# 2_waffling60-MX_matrix.net
KiCad netlist of a schematic drawn in Altium Designer
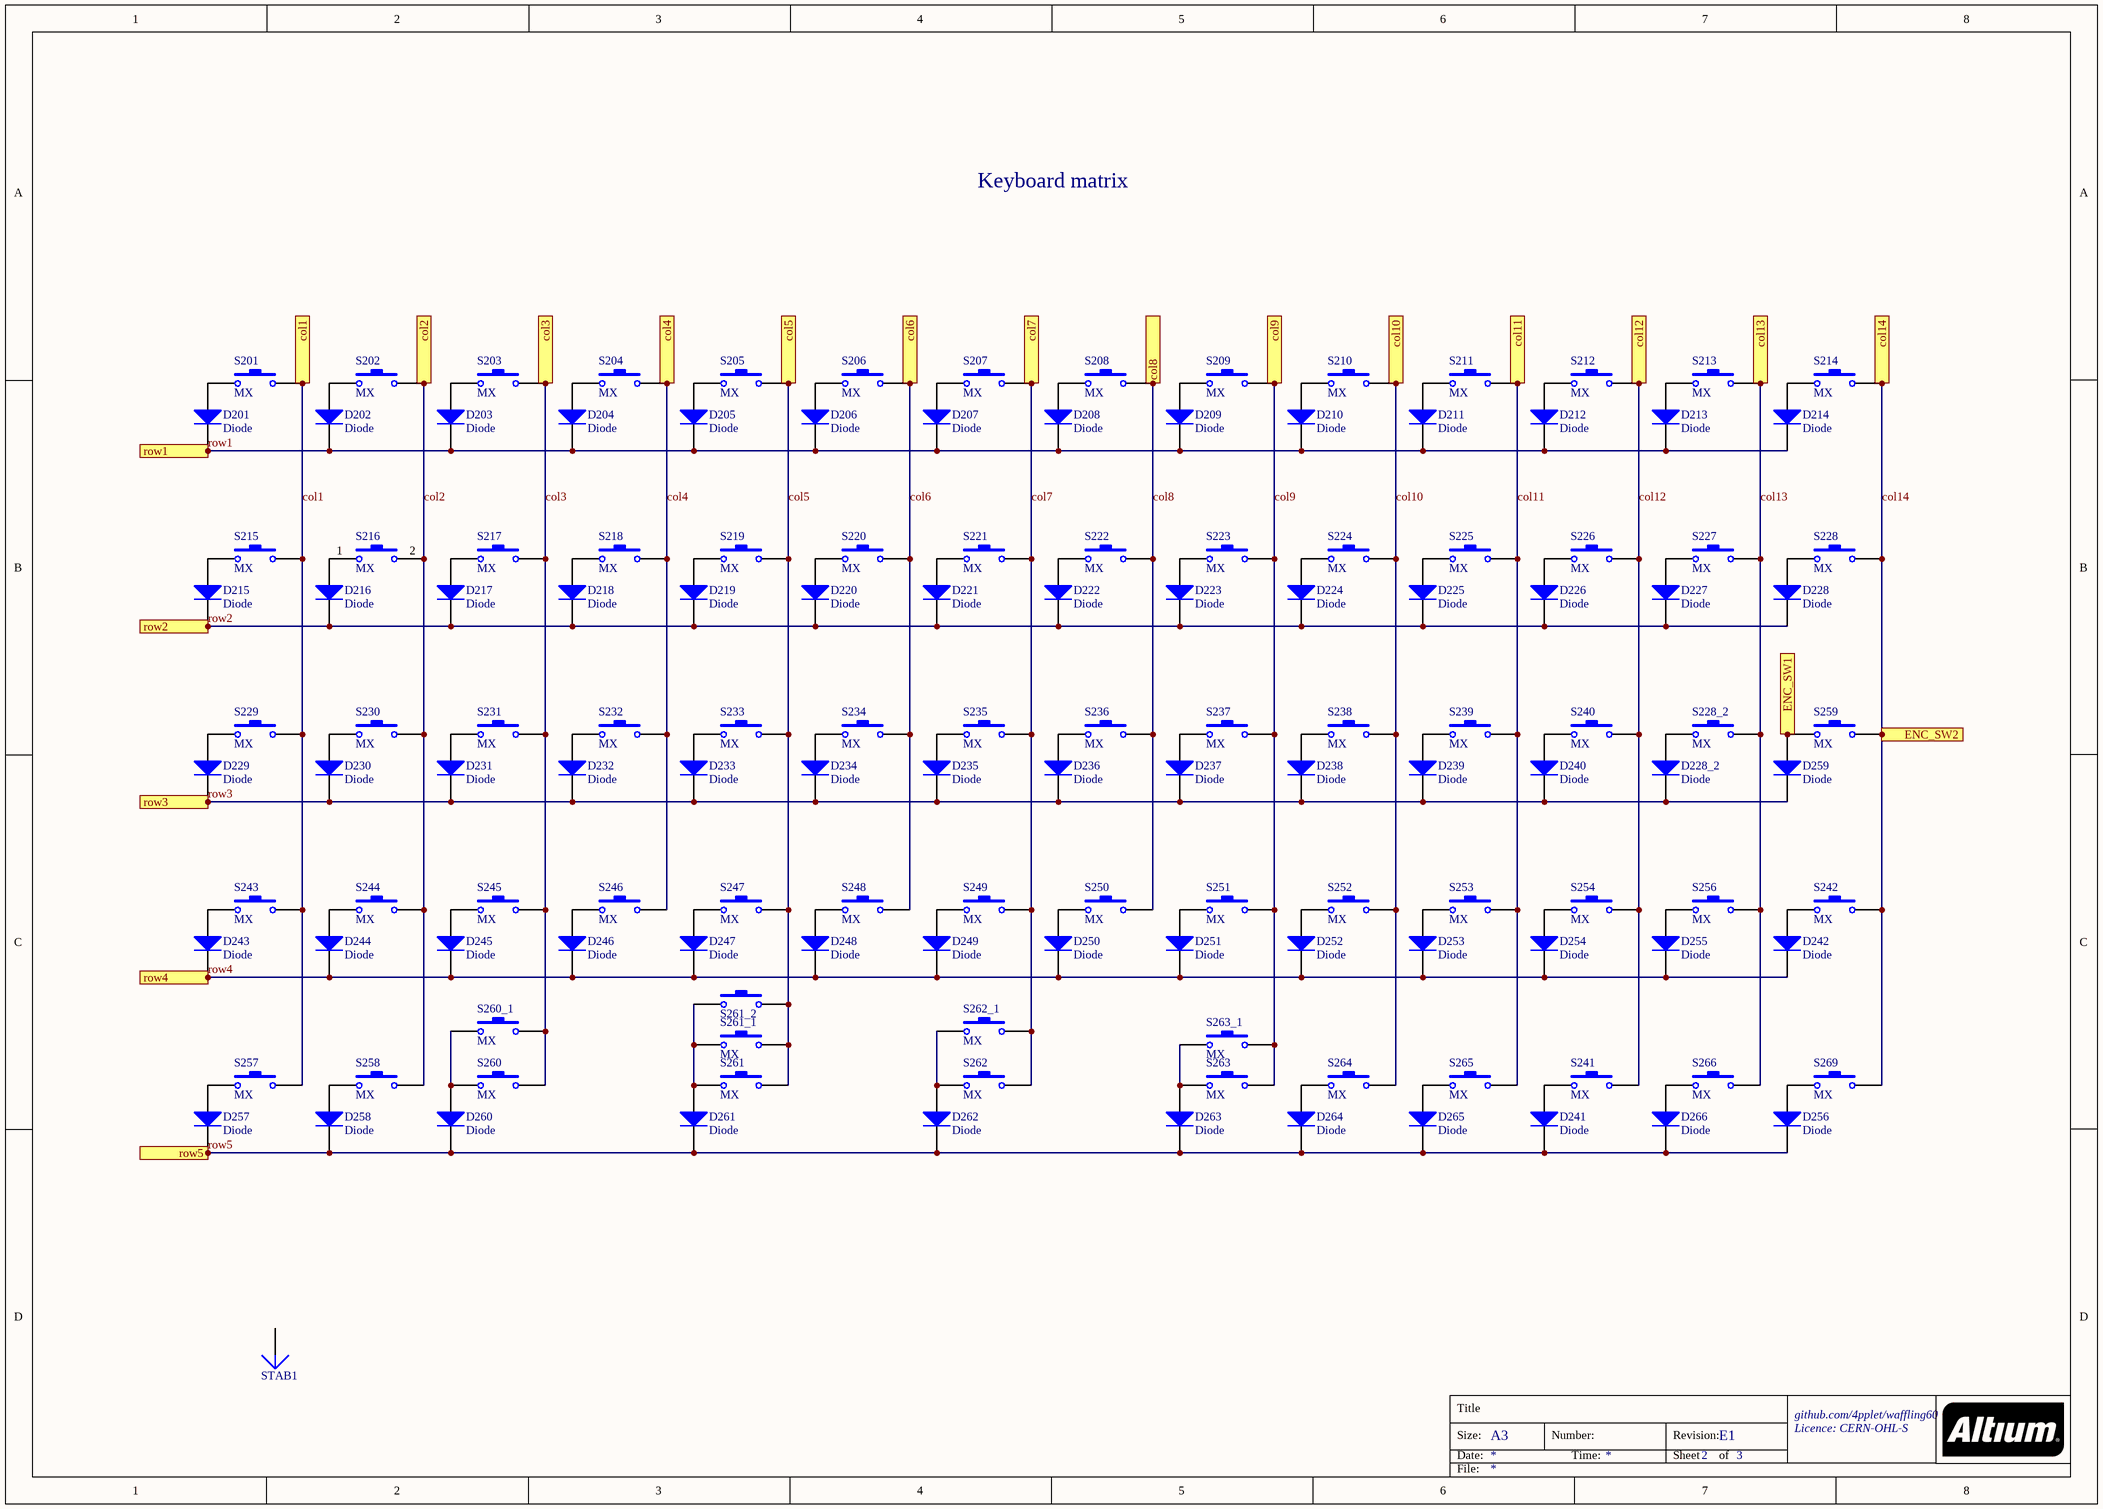
[diagram p0: 2_waffling60-MX_matrix.SchDoc]

(export (version "E")
  (design (tool "Eeschema 10.0.6"))
  (components
    (comp (ref "D201")
      (value "Diode")
      (footprint "SOD-123")
      (description "Default Diode")
      (fields (field (name "LCSC PART #") "C81598") (field (name "MRF.PART") "1N4148W"))
      (libsource (lib "Miscellaneous Devices") (part "Diode"))
    )
    (comp (ref "D202")
      (value "Diode")
      (footprint "SOD-123")
      (description "Default Diode")
      (fields (field (name "LCSC PART #") "C81598") (field (name "MRF.PART") "1N4148W"))
      (libsource (lib "Miscellaneous Devices") (part "Diode"))
    )
    (comp (ref "D203")
      (value "Diode")
      (footprint "SOD-123")
      (description "Default Diode")
      (fields (field (name "LCSC PART #") "C81598") (field (name "MRF.PART") "1N4148W"))
      (libsource (lib "Miscellaneous Devices") (part "Diode"))
    )
    (comp (ref "D204")
      (value "Diode")
      (footprint "SOD-123")
      (description "Default Diode")
      (fields (field (name "LCSC PART #") "C81598") (field (name "MRF.PART") "1N4148W"))
      (libsource (lib "Miscellaneous Devices") (part "Diode"))
    )
    (comp (ref "D205")
      (value "Diode")
      (footprint "SOD-123")
      (description "Default Diode")
      (fields (field (name "LCSC PART #") "C81598") (field (name "MRF.PART") "1N4148W"))
      (libsource (lib "Miscellaneous Devices") (part "Diode"))
    )
    (comp (ref "D206")
      (value "Diode")
      (footprint "SOD-123")
      (description "Default Diode")
      (fields (field (name "LCSC PART #") "C81598") (field (name "MRF.PART") "1N4148W"))
      (libsource (lib "Miscellaneous Devices") (part "Diode"))
    )
    (comp (ref "D207")
      (value "Diode")
      (footprint "SOD-123")
      (description "Default Diode")
      (fields (field (name "LCSC PART #") "C81598") (field (name "MRF.PART") "1N4148W"))
      (libsource (lib "Miscellaneous Devices") (part "Diode"))
    )
    (comp (ref "D208")
      (value "Diode")
      (footprint "SOD-123")
      (description "Default Diode")
      (fields (field (name "LCSC PART #") "C81598") (field (name "MRF.PART") "1N4148W"))
      (libsource (lib "Miscellaneous Devices") (part "Diode"))
    )
    (comp (ref "D209")
      (value "Diode")
      (footprint "SOD-123")
      (description "Default Diode")
      (fields (field (name "LCSC PART #") "C81598") (field (name "MRF.PART") "1N4148W"))
      (libsource (lib "Miscellaneous Devices") (part "Diode"))
    )
    (comp (ref "D210")
      (value "Diode")
      (footprint "SOD-123")
      (description "Default Diode")
      (fields (field (name "LCSC PART #") "C81598") (field (name "MRF.PART") "1N4148W"))
      (libsource (lib "Miscellaneous Devices") (part "Diode"))
    )
    (comp (ref "D211")
      (value "Diode")
      (footprint "SOD-123")
      (description "Default Diode")
      (fields (field (name "LCSC PART #") "C81598") (field (name "MRF.PART") "1N4148W"))
      (libsource (lib "Miscellaneous Devices") (part "Diode"))
    )
    (comp (ref "D212")
      (value "Diode")
      (footprint "SOD-123")
      (description "Default Diode")
      (fields (field (name "LCSC PART #") "C81598") (field (name "MRF.PART") "1N4148W"))
      (libsource (lib "Miscellaneous Devices") (part "Diode"))
    )
    (comp (ref "D213")
      (value "Diode")
      (footprint "SOD-123")
      (description "Default Diode")
      (fields (field (name "LCSC PART #") "C81598") (field (name "MRF.PART") "1N4148W"))
      (libsource (lib "Miscellaneous Devices") (part "Diode"))
    )
    (comp (ref "D214")
      (value "Diode")
      (footprint "SOD-123")
      (description "Default Diode")
      (fields (field (name "LCSC PART #") "C81598") (field (name "MRF.PART") "1N4148W"))
      (libsource (lib "Miscellaneous Devices") (part "Diode"))
    )
    (comp (ref "D215")
      (value "Diode")
      (footprint "SOD-123")
      (description "Default Diode")
      (fields (field (name "LCSC PART #") "C81598") (field (name "MRF.PART") "1N4148W"))
      (libsource (lib "Miscellaneous Devices") (part "Diode"))
    )
    (comp (ref "D216")
      (value "Diode")
      (footprint "SOD-123")
      (description "Default Diode")
      (fields (field (name "LCSC PART #") "C81598") (field (name "MRF.PART") "1N4148W"))
      (libsource (lib "Miscellaneous Devices") (part "Diode"))
    )
    (comp (ref "D217")
      (value "Diode")
      (footprint "SOD-123")
      (description "Default Diode")
      (fields (field (name "LCSC PART #") "C81598") (field (name "MRF.PART") "1N4148W"))
      (libsource (lib "Miscellaneous Devices") (part "Diode"))
    )
    (comp (ref "D218")
      (value "Diode")
      (footprint "SOD-123")
      (description "Default Diode")
      (fields (field (name "LCSC PART #") "C81598") (field (name "MRF.PART") "1N4148W"))
      (libsource (lib "Miscellaneous Devices") (part "Diode"))
    )
    (comp (ref "D219")
      (value "Diode")
      (footprint "SOD-123")
      (description "Default Diode")
      (fields (field (name "LCSC PART #") "C81598") (field (name "MRF.PART") "1N4148W"))
      (libsource (lib "Miscellaneous Devices") (part "Diode"))
    )
    (comp (ref "D220")
      (value "Diode")
      (footprint "SOD-123")
      (description "Default Diode")
      (fields (field (name "LCSC PART #") "C81598") (field (name "MRF.PART") "1N4148W"))
      (libsource (lib "Miscellaneous Devices") (part "Diode"))
    )
    (comp (ref "D221")
      (value "Diode")
      (footprint "SOD-123")
      (description "Default Diode")
      (fields (field (name "LCSC PART #") "C81598") (field (name "MRF.PART") "1N4148W"))
      (libsource (lib "Miscellaneous Devices") (part "Diode"))
    )
    (comp (ref "D222")
      (value "Diode")
      (footprint "SOD-123")
      (description "Default Diode")
      (fields (field (name "LCSC PART #") "C81598") (field (name "MRF.PART") "1N4148W"))
      (libsource (lib "Miscellaneous Devices") (part "Diode"))
    )
    (comp (ref "D223")
      (value "Diode")
      (footprint "SOD-123")
      (description "Default Diode")
      (fields (field (name "LCSC PART #") "C81598") (field (name "MRF.PART") "1N4148W"))
      (libsource (lib "Miscellaneous Devices") (part "Diode"))
    )
    (comp (ref "D224")
      (value "Diode")
      (footprint "SOD-123")
      (description "Default Diode")
      (fields (field (name "LCSC PART #") "C81598") (field (name "MRF.PART") "1N4148W"))
      (libsource (lib "Miscellaneous Devices") (part "Diode"))
    )
    (comp (ref "D225")
      (value "Diode")
      (footprint "SOD-123")
      (description "Default Diode")
      (fields (field (name "LCSC PART #") "C81598") (field (name "MRF.PART") "1N4148W"))
      (libsource (lib "Miscellaneous Devices") (part "Diode"))
    )
    (comp (ref "D226")
      (value "Diode")
      (footprint "SOD-123")
      (description "Default Diode")
      (fields (field (name "LCSC PART #") "C81598") (field (name "MRF.PART") "1N4148W"))
      (libsource (lib "Miscellaneous Devices") (part "Diode"))
    )
    (comp (ref "D227")
      (value "Diode")
      (footprint "SOD-123")
      (description "Default Diode")
      (fields (field (name "LCSC PART #") "C81598") (field (name "MRF.PART") "1N4148W"))
      (libsource (lib "Miscellaneous Devices") (part "Diode"))
    )
    (comp (ref "D228")
      (value "Diode")
      (footprint "SOD-123")
      (description "Default Diode")
      (fields (field (name "LCSC PART #") "C81598") (field (name "MRF.PART") "1N4148W"))
      (libsource (lib "Miscellaneous Devices") (part "Diode"))
    )
    (comp (ref "D228_2")
      (value "Diode")
      (footprint "SOD-123")
      (description "Default Diode")
      (fields (field (name "LCSC PART #") "C81598") (field (name "MRF.PART") "1N4148W"))
      (libsource (lib "Miscellaneous Devices") (part "Diode"))
    )
    (comp (ref "D229")
      (value "Diode")
      (footprint "SOD-123")
      (description "Default Diode")
      (fields (field (name "LCSC PART #") "C81598") (field (name "MRF.PART") "1N4148W"))
      (libsource (lib "Miscellaneous Devices") (part "Diode"))
    )
    (comp (ref "D230")
      (value "Diode")
      (footprint "SOD-123")
      (description "Default Diode")
      (fields (field (name "LCSC PART #") "C81598") (field (name "MRF.PART") "1N4148W"))
      (libsource (lib "Miscellaneous Devices") (part "Diode"))
    )
    (comp (ref "D231")
      (value "Diode")
      (footprint "SOD-123")
      (description "Default Diode")
      (fields (field (name "LCSC PART #") "C81598") (field (name "MRF.PART") "1N4148W"))
      (libsource (lib "Miscellaneous Devices") (part "Diode"))
    )
    (comp (ref "D232")
      (value "Diode")
      (footprint "SOD-123")
      (description "Default Diode")
      (fields (field (name "LCSC PART #") "C81598") (field (name "MRF.PART") "1N4148W"))
      (libsource (lib "Miscellaneous Devices") (part "Diode"))
    )
    (comp (ref "D233")
      (value "Diode")
      (footprint "SOD-123")
      (description "Default Diode")
      (fields (field (name "LCSC PART #") "C81598") (field (name "MRF.PART") "1N4148W"))
      (libsource (lib "Miscellaneous Devices") (part "Diode"))
    )
    (comp (ref "D234")
      (value "Diode")
      (footprint "SOD-123")
      (description "Default Diode")
      (fields (field (name "LCSC PART #") "C81598") (field (name "MRF.PART") "1N4148W"))
      (libsource (lib "Miscellaneous Devices") (part "Diode"))
    )
    (comp (ref "D235")
      (value "Diode")
      (footprint "SOD-123")
      (description "Default Diode")
      (fields (field (name "LCSC PART #") "C81598") (field (name "MRF.PART") "1N4148W"))
      (libsource (lib "Miscellaneous Devices") (part "Diode"))
    )
    (comp (ref "D236")
      (value "Diode")
      (footprint "SOD-123")
      (description "Default Diode")
      (fields (field (name "LCSC PART #") "C81598") (field (name "MRF.PART") "1N4148W"))
      (libsource (lib "Miscellaneous Devices") (part "Diode"))
    )
    (comp (ref "D237")
      (value "Diode")
      (footprint "SOD-123")
      (description "Default Diode")
      (fields (field (name "LCSC PART #") "C81598") (field (name "MRF.PART") "1N4148W"))
      (libsource (lib "Miscellaneous Devices") (part "Diode"))
    )
    (comp (ref "D238")
      (value "Diode")
      (footprint "SOD-123")
      (description "Default Diode")
      (fields (field (name "LCSC PART #") "C81598") (field (name "MRF.PART") "1N4148W"))
      (libsource (lib "Miscellaneous Devices") (part "Diode"))
    )
    (comp (ref "D239")
      (value "Diode")
      (footprint "SOD-123")
      (description "Default Diode")
      (fields (field (name "LCSC PART #") "C81598") (field (name "MRF.PART") "1N4148W"))
      (libsource (lib "Miscellaneous Devices") (part "Diode"))
    )
    (comp (ref "D240")
      (value "Diode")
      (footprint "SOD-123")
      (description "Default Diode")
      (fields (field (name "LCSC PART #") "C81598") (field (name "MRF.PART") "1N4148W"))
      (libsource (lib "Miscellaneous Devices") (part "Diode"))
    )
    (comp (ref "D241")
      (value "Diode")
      (footprint "SOD-123")
      (description "Default Diode")
      (fields (field (name "LCSC PART #") "C81598") (field (name "MRF.PART") "1N4148W"))
      (libsource (lib "Miscellaneous Devices") (part "Diode"))
    )
    (comp (ref "D242")
      (value "Diode")
      (footprint "SOD-123")
      (description "Default Diode")
      (fields (field (name "LCSC PART #") "C81598") (field (name "MRF.PART") "1N4148W"))
      (libsource (lib "Miscellaneous Devices") (part "Diode"))
    )
    (comp (ref "D243")
      (value "Diode")
      (footprint "SOD-123")
      (description "Default Diode")
      (fields (field (name "LCSC PART #") "C81598") (field (name "MRF.PART") "1N4148W"))
      (libsource (lib "Miscellaneous Devices") (part "Diode"))
    )
    (comp (ref "D244")
      (value "Diode")
      (footprint "SOD-123")
      (description "Default Diode")
      (fields (field (name "LCSC PART #") "C81598") (field (name "MRF.PART") "1N4148W"))
      (libsource (lib "Miscellaneous Devices") (part "Diode"))
    )
    (comp (ref "D245")
      (value "Diode")
      (footprint "SOD-123")
      (description "Default Diode")
      (fields (field (name "LCSC PART #") "C81598") (field (name "MRF.PART") "1N4148W"))
      (libsource (lib "Miscellaneous Devices") (part "Diode"))
    )
    (comp (ref "D246")
      (value "Diode")
      (footprint "SOD-123")
      (description "Default Diode")
      (fields (field (name "LCSC PART #") "C81598") (field (name "MRF.PART") "1N4148W"))
      (libsource (lib "Miscellaneous Devices") (part "Diode"))
    )
    (comp (ref "D247")
      (value "Diode")
      (footprint "SOD-123")
      (description "Default Diode")
      (fields (field (name "LCSC PART #") "C81598") (field (name "MRF.PART") "1N4148W"))
      (libsource (lib "Miscellaneous Devices") (part "Diode"))
    )
    (comp (ref "D248")
      (value "Diode")
      (footprint "SOD-123")
      (description "Default Diode")
      (fields (field (name "LCSC PART #") "C81598") (field (name "MRF.PART") "1N4148W"))
      (libsource (lib "Miscellaneous Devices") (part "Diode"))
    )
    (comp (ref "D249")
      (value "Diode")
      (footprint "SOD-123")
      (description "Default Diode")
      (fields (field (name "LCSC PART #") "C81598") (field (name "MRF.PART") "1N4148W"))
      (libsource (lib "Miscellaneous Devices") (part "Diode"))
    )
    (comp (ref "D250")
      (value "Diode")
      (footprint "SOD-123")
      (description "Default Diode")
      (fields (field (name "LCSC PART #") "C81598") (field (name "MRF.PART") "1N4148W"))
      (libsource (lib "Miscellaneous Devices") (part "Diode"))
    )
    (comp (ref "D251")
      (value "Diode")
      (footprint "SOD-123")
      (description "Default Diode")
      (fields (field (name "LCSC PART #") "C81598") (field (name "MRF.PART") "1N4148W"))
      (libsource (lib "Miscellaneous Devices") (part "Diode"))
    )
    (comp (ref "D252")
      (value "Diode")
      (footprint "SOD-123")
      (description "Default Diode")
      (fields (field (name "LCSC PART #") "C81598") (field (name "MRF.PART") "1N4148W"))
      (libsource (lib "Miscellaneous Devices") (part "Diode"))
    )
    (comp (ref "D253")
      (value "Diode")
      (footprint "SOD-123")
      (description "Default Diode")
      (fields (field (name "LCSC PART #") "C81598") (field (name "MRF.PART") "1N4148W"))
      (libsource (lib "Miscellaneous Devices") (part "Diode"))
    )
    (comp (ref "D254")
      (value "Diode")
      (footprint "SOD-123")
      (description "Default Diode")
      (fields (field (name "LCSC PART #") "C81598") (field (name "MRF.PART") "1N4148W"))
      (libsource (lib "Miscellaneous Devices") (part "Diode"))
    )
    (comp (ref "D255")
      (value "Diode")
      (footprint "SOD-123")
      (description "Default Diode")
      (fields (field (name "LCSC PART #") "C81598") (field (name "MRF.PART") "1N4148W"))
      (libsource (lib "Miscellaneous Devices") (part "Diode"))
    )
    (comp (ref "D256")
      (value "Diode")
      (footprint "SOD-123")
      (description "Default Diode")
      (fields (field (name "LCSC PART #") "C81598") (field (name "MRF.PART") "1N4148W"))
      (libsource (lib "Miscellaneous Devices") (part "Diode"))
    )
    (comp (ref "D257")
      (value "Diode")
      (footprint "SOD-123")
      (description "Default Diode")
      (fields (field (name "LCSC PART #") "C81598") (field (name "MRF.PART") "1N4148W"))
      (libsource (lib "Miscellaneous Devices") (part "Diode"))
    )
    (comp (ref "D258")
      (value "Diode")
      (footprint "SOD-123")
      (description "Default Diode")
      (fields (field (name "LCSC PART #") "C81598") (field (name "MRF.PART") "1N4148W"))
      (libsource (lib "Miscellaneous Devices") (part "Diode"))
    )
    (comp (ref "D259")
      (value "Diode")
      (footprint "SOD-123")
      (description "Default Diode")
      (fields (field (name "LCSC PART #") "C81598") (field (name "MRF.PART") "1N4148W"))
      (libsource (lib "Miscellaneous Devices") (part "Diode"))
    )
    (comp (ref "D260")
      (value "Diode")
      (footprint "SOD-123")
      (description "Default Diode")
      (fields (field (name "LCSC PART #") "C81598") (field (name "MRF.PART") "1N4148W"))
      (libsource (lib "Miscellaneous Devices") (part "Diode"))
    )
    (comp (ref "D261")
      (value "Diode")
      (footprint "SOD-123")
      (description "Default Diode")
      (fields (field (name "LCSC PART #") "C81598") (field (name "MRF.PART") "1N4148W"))
      (libsource (lib "Miscellaneous Devices") (part "Diode"))
    )
    (comp (ref "D262")
      (value "Diode")
      (footprint "SOD-123")
      (description "Default Diode")
      (fields (field (name "LCSC PART #") "C81598") (field (name "MRF.PART") "1N4148W"))
      (libsource (lib "Miscellaneous Devices") (part "Diode"))
    )
    (comp (ref "D263")
      (value "Diode")
      (footprint "SOD-123")
      (description "Default Diode")
      (fields (field (name "LCSC PART #") "C81598") (field (name "MRF.PART") "1N4148W"))
      (libsource (lib "Miscellaneous Devices") (part "Diode"))
    )
    (comp (ref "D264")
      (value "Diode")
      (footprint "SOD-123")
      (description "Default Diode")
      (fields (field (name "LCSC PART #") "C81598") (field (name "MRF.PART") "1N4148W"))
      (libsource (lib "Miscellaneous Devices") (part "Diode"))
    )
    (comp (ref "D265")
      (value "Diode")
      (footprint "SOD-123")
      (description "Default Diode")
      (fields (field (name "LCSC PART #") "C81598") (field (name "MRF.PART") "1N4148W"))
      (libsource (lib "Miscellaneous Devices") (part "Diode"))
    )
    (comp (ref "D266")
      (value "Diode")
      (footprint "SOD-123")
      (description "Default Diode")
      (fields (field (name "LCSC PART #") "C81598") (field (name "MRF.PART") "1N4148W"))
      (libsource (lib "Miscellaneous Devices") (part "Diode"))
    )
    (comp (ref "S201")
      (value "MX")
      (footprint "MX-switch - switched pol")
      (description "Switch")
      (libsource (lib "Miscellaneous Devices") (part "SW-PB"))
    )
    (comp (ref "S202")
      (value "MX")
      (footprint "MX-switch")
      (description "Switch")
      (libsource (lib "Miscellaneous Devices") (part "SW-PB"))
    )
    (comp (ref "S203")
      (value "MX")
      (footprint "MX-switch - switched pol")
      (description "Switch")
      (libsource (lib "Miscellaneous Devices") (part "SW-PB"))
    )
    (comp (ref "S204")
      (value "MX")
      (footprint "MX-switch - switched pol")
      (description "Switch")
      (libsource (lib "Miscellaneous Devices") (part "SW-PB"))
    )
    (comp (ref "S205")
      (value "MX")
      (footprint "MX-switch - switched pol")
      (description "Switch")
      (libsource (lib "Miscellaneous Devices") (part "SW-PB"))
    )
    (comp (ref "S206")
      (value "MX")
      (footprint "MX-switch - switched pol")
      (description "Switch")
      (libsource (lib "Miscellaneous Devices") (part "SW-PB"))
    )
    (comp (ref "S207")
      (value "MX")
      (footprint "MX-switch - switched pol")
      (description "Switch")
      (libsource (lib "Miscellaneous Devices") (part "SW-PB"))
    )
    (comp (ref "S208")
      (value "MX")
      (footprint "MX-switch - switched pol")
      (description "Switch")
      (libsource (lib "Miscellaneous Devices") (part "SW-PB"))
    )
    (comp (ref "S209")
      (value "MX")
      (footprint "MX-switch - switched pol")
      (description "Switch")
      (libsource (lib "Miscellaneous Devices") (part "SW-PB"))
    )
    (comp (ref "S210")
      (value "MX")
      (footprint "MX-switch - switched pol")
      (description "Switch")
      (libsource (lib "Miscellaneous Devices") (part "SW-PB"))
    )
    (comp (ref "S211")
      (value "MX")
      (footprint "MX-switch - switched pol")
      (description "Switch")
      (libsource (lib "Miscellaneous Devices") (part "SW-PB"))
    )
    (comp (ref "S212")
      (value "MX")
      (footprint "MX-switch - switched pol")
      (description "Switch")
      (libsource (lib "Miscellaneous Devices") (part "SW-PB"))
    )
    (comp (ref "S213")
      (value "MX")
      (footprint "MX-switch - switched pol")
      (description "Switch")
      (libsource (lib "Miscellaneous Devices") (part "SW-PB"))
    )
    (comp (ref "S214")
      (value "MX")
      (footprint "MX-switch")
      (description "Switch")
      (libsource (lib "Miscellaneous Devices") (part "SW-PB"))
    )
    (comp (ref "S215")
      (value "MX")
      (footprint "MX-switch - switched pol")
      (description "TAB")
      (libsource (lib "Miscellaneous Devices") (part "SW-PB"))
    )
    (comp (ref "S216")
      (value "MX")
      (footprint "MX-switch")
      (description "Switch")
      (libsource (lib "") (part "SW-PB_2"))
    )
    (comp (ref "S217")
      (value "MX")
      (footprint "MX-switch - switched pol")
      (description "Switch")
      (libsource (lib "Miscellaneous Devices") (part "SW-PB"))
    )
    (comp (ref "S218")
      (value "MX")
      (footprint "MX-switch - switched pol")
      (description "Switch")
      (libsource (lib "Miscellaneous Devices") (part "SW-PB"))
    )
    (comp (ref "S219")
      (value "MX")
      (footprint "MX-switch - switched pol")
      (description "Switch")
      (libsource (lib "Miscellaneous Devices") (part "SW-PB"))
    )
    (comp (ref "S220")
      (value "MX")
      (footprint "MX-switch")
      (description "Switch")
      (libsource (lib "Miscellaneous Devices") (part "SW-PB"))
    )
    (comp (ref "S221")
      (value "MX")
      (footprint "MX-switch - switched pol")
      (description "Switch")
      (libsource (lib "Miscellaneous Devices") (part "SW-PB"))
    )
    (comp (ref "S222")
      (value "MX")
      (footprint "MX-switch")
      (description "Switch")
      (libsource (lib "Miscellaneous Devices") (part "SW-PB"))
    )
    (comp (ref "S223")
      (value "MX")
      (footprint "MX-switch - switched pol")
      (description "Switch")
      (libsource (lib "Miscellaneous Devices") (part "SW-PB"))
    )
    (comp (ref "S224")
      (value "MX")
      (footprint "MX-switch - switched pol")
      (description "Switch")
      (libsource (lib "Miscellaneous Devices") (part "SW-PB"))
    )
    (comp (ref "S225")
      (value "MX")
      (footprint "MX-switch - switched pol")
      (description "Switch")
      (libsource (lib "Miscellaneous Devices") (part "SW-PB"))
    )
    (comp (ref "S226")
      (value "MX")
      (footprint "MX-switch")
      (description "Switch")
      (libsource (lib "Miscellaneous Devices") (part "SW-PB"))
    )
    (comp (ref "S227")
      (value "MX")
      (footprint "MX-switch")
      (description "Switch")
      (libsource (lib "Miscellaneous Devices") (part "SW-PB"))
    )
    (comp (ref "S228")
      (value "MX")
      (footprint "MX-switch - 1.5U")
      (description "Switch")
      (libsource (lib "Miscellaneous Devices") (part "SW-PB"))
    )
    (comp (ref "S228_2")
      (value "MX")
      (footprint "MX-switch")
      (description "Switch")
      (libsource (lib "Miscellaneous Devices") (part "SW-PB"))
    )
    (comp (ref "S229")
      (value "MX")
      (footprint "MX-switch - CAPS")
      (description "Switch")
      (libsource (lib "Miscellaneous Devices") (part "SW-PB"))
    )
    (comp (ref "S230")
      (value "MX")
      (footprint "MX-switch")
      (description "Switch")
      (libsource (lib "Miscellaneous Devices") (part "SW-PB"))
    )
    (comp (ref "S231")
      (value "MX")
      (footprint "MX-switch - switched pol")
      (description "Switch")
      (libsource (lib "Miscellaneous Devices") (part "SW-PB"))
    )
    (comp (ref "S232")
      (value "MX")
      (footprint "MX-switch - switched pol")
      (description "Switch")
      (libsource (lib "Miscellaneous Devices") (part "SW-PB"))
    )
    (comp (ref "S233")
      (value "MX")
      (footprint "MX-switch - switched pol")
      (description "Switch")
      (libsource (lib "Miscellaneous Devices") (part "SW-PB"))
    )
    (comp (ref "S234")
      (value "MX")
      (footprint "MX-switch - switched pol")
      (description "Switch")
      (libsource (lib "Miscellaneous Devices") (part "SW-PB"))
    )
    (comp (ref "S235")
      (value "MX")
      (footprint "MX-switch - switched pol")
      (description "Switch")
      (libsource (lib "Miscellaneous Devices") (part "SW-PB"))
    )
    (comp (ref "S236")
      (value "MX")
      (footprint "MX-switch - switched pol")
      (description "Switch")
      (libsource (lib "Miscellaneous Devices") (part "SW-PB"))
    )
    (comp (ref "S237")
      (value "MX")
      (footprint "MX-switch - switched pol")
      (description "Switch")
      (libsource (lib "Miscellaneous Devices") (part "SW-PB"))
    )
    (comp (ref "S238")
      (value "MX")
      (footprint "MX-switch - switched pol")
      (description "Switch")
      (libsource (lib "Miscellaneous Devices") (part "SW-PB"))
    )
    (comp (ref "S239")
      (value "MX")
      (footprint "MX-switch - switched pol")
      (description "Switch")
      (libsource (lib "Miscellaneous Devices") (part "SW-PB"))
    )
    (comp (ref "S240")
      (value "MX")
      (footprint "MX-switch - switched pol")
      (description "Switch")
      (libsource (lib "Miscellaneous Devices") (part "SW-PB"))
    )
    (comp (ref "S241")
      (value "MX")
      (footprint "MX-switch - 1u MOD-R")
      (description "Switch")
      (libsource (lib "Miscellaneous Devices") (part "SW-PB"))
    )
    (comp (ref "S242")
      (value "MX")
      (footprint "MX-switch - Enter - Rotated Stab")
      (description "Switch")
      (libsource (lib "Miscellaneous Devices") (part "SW-PB"))
    )
    (comp (ref "S243")
      (value "MX")
      (footprint "MX-switch - Left shift")
      (description "Switch")
      (libsource (lib "Miscellaneous Devices") (part "SW-PB"))
    )
    (comp (ref "S244")
      (value "MX")
      (footprint "MX-switch")
      (description "Switch")
      (libsource (lib "Miscellaneous Devices") (part "SW-PB"))
    )
    (comp (ref "S245")
      (value "MX")
      (footprint "MX-switch - switched pol")
      (description "Switch")
      (libsource (lib "Miscellaneous Devices") (part "SW-PB"))
    )
    (comp (ref "S246")
      (value "MX")
      (footprint "MX-switch - switched pol")
      (description "Switch")
      (libsource (lib "Miscellaneous Devices") (part "SW-PB"))
    )
    (comp (ref "S247")
      (value "MX")
      (footprint "MX-switch - switched pol")
      (description "Switch")
      (libsource (lib "Miscellaneous Devices") (part "SW-PB"))
    )
    (comp (ref "S248")
      (value "MX")
      (footprint "MX-switch - switched pol")
      (description "Switch")
      (libsource (lib "Miscellaneous Devices") (part "SW-PB"))
    )
    (comp (ref "S249")
      (value "MX")
      (footprint "MX-switch - switched pol")
      (description "Switch")
      (libsource (lib "Miscellaneous Devices") (part "SW-PB"))
    )
    (comp (ref "S250")
      (value "MX")
      (footprint "MX-switch - switched pol")
      (description "Switch")
      (libsource (lib "Miscellaneous Devices") (part "SW-PB"))
    )
    (comp (ref "S251")
      (value "MX")
      (footprint "MX-switch - switched pol")
      (description "Switch")
      (libsource (lib "Miscellaneous Devices") (part "SW-PB"))
    )
    (comp (ref "S252")
      (value "MX")
      (footprint "MX-switch - switched pol")
      (description "Switch")
      (libsource (lib "Miscellaneous Devices") (part "SW-PB"))
    )
    (comp (ref "S253")
      (value "MX")
      (footprint "MX-switch - switched pol")
      (description "Switch")
      (libsource (lib "Miscellaneous Devices") (part "SW-PB"))
    )
    (comp (ref "S254")
      (value "MX")
      (footprint "MX-switch - switched pol")
      (description "Switch")
      (libsource (lib "Miscellaneous Devices") (part "SW-PB"))
    )
    (comp (ref "S256")
      (value "MX")
      (footprint "MX-switch - right shift")
      (description "Switch")
      (libsource (lib "Miscellaneous Devices") (part "SW-PB"))
    )
    (comp (ref "S257")
      (value "MX")
      (footprint "MX-switch - 1.5u MOD-L")
      (description "Switch")
      (libsource (lib "Miscellaneous Devices") (part "SW-PB"))
    )
    (comp (ref "S258")
      (value "MX")
      (footprint "MX-switch - 1u MOD-L")
      (description "Switch")
      (libsource (lib "Miscellaneous Devices") (part "SW-PB"))
    )
    (comp (ref "S259")
      (value "MX")
      (footprint "MX-switch - backspace")
      (description "Switch")
      (libsource (lib "Miscellaneous Devices") (part "SW-PB"))
    )
    (comp (ref "S260")
      (value "MX")
      (footprint "MX-switch - 1.5u MOD-L")
      (description "Switch")
      (libsource (lib "Miscellaneous Devices") (part "SW-PB"))
    )
    (comp (ref "S260_1")
      (value "MX")
      (footprint "MX-switch")
      (description "Switch")
      (libsource (lib "Miscellaneous Devices") (part "SW-PB"))
    )
    (comp (ref "S261")
      (value "MX")
      (footprint "MX-SWITCH - L SPLIT SPACE_V2")
      (description "Switch")
      (libsource (lib "Miscellaneous Devices") (part "SW-PB"))
    )
    (comp (ref "S261_1")
      (value "MX")
      (footprint "MX-switch - 3U - rotated stab")
      (description "Switch")
      (libsource (lib "Miscellaneous Devices") (part "SW-PB"))
    )
    (comp (ref "S261_2")
      (value "Comment")
      (footprint "MX-switch")
      (description "Switch")
      (libsource (lib "") (part "SW-PB_1"))
    )
    (comp (ref "S262")
      (value "MX")
      (footprint "MX-switch - Space_V3")
      (description "Switch")
      (libsource (lib "Miscellaneous Devices") (part "SW-PB"))
    )
    (comp (ref "S262_1")
      (value "MX")
      (footprint "MX-switch - switched pol")
      (description "Switch")
      (libsource (lib "Miscellaneous Devices") (part "SW-PB"))
    )
    (comp (ref "S263")
      (value "MX")
      (footprint "MX-SWITCH - R SPLIT SPACE_V2")
      (description "Switch")
      (libsource (lib "Miscellaneous Devices") (part "SW-PB"))
    )
    (comp (ref "S263_1")
      (value "MX")
      (footprint "MX-switch - 3U - rotated stab")
      (description "Switch")
      (libsource (lib "Miscellaneous Devices") (part "SW-PB"))
    )
    (comp (ref "S264")
      (value "MX")
      (footprint "MX-switch - switched pol")
      (description "Switch")
      (libsource (lib "Miscellaneous Devices") (part "SW-PB"))
    )
    (comp (ref "S265")
      (value "MX")
      (footprint "MX-switch - 1.5u MOD-R")
      (description "Switch")
      (libsource (lib "Miscellaneous Devices") (part "SW-PB"))
    )
    (comp (ref "S266")
      (value "MX")
      (footprint "MX-switch - 1.5u MOD-R")
      (description "Switch")
      (libsource (lib "Miscellaneous Devices") (part "SW-PB"))
    )
    (comp (ref "S269")
      (value "MX")
      (footprint "MX-switch")
      (description "Switch")
      (libsource (lib "Miscellaneous Devices") (part "SW-PB"))
    )
    (comp (ref "STAB1")
      (value "Plug")
      (footprint "Stab 10U")
      (libsource (lib "Miscellaneous Connectors") (part "Plug"))
    )
  )
  (nets
    (net (code "1") (name "/ENC_SW1") (class "Default")
      (node (ref "D259") (pin "1") (pinfunction "A_1") (pintype "passive"))
      (node (ref "S259") (pin "1") (pinfunction "1_1") (pintype "passive"))
    )
    (net (code "2") (name "/col1") (class "Default")
      (node (ref "S201") (pin "2") (pinfunction "2_2") (pintype "passive"))
      (node (ref "S215") (pin "2") (pinfunction "2_2") (pintype "passive"))
      (node (ref "S229") (pin "1") (pinfunction "1_1") (pintype "passive"))
      (node (ref "S243") (pin "2") (pinfunction "2_2") (pintype "passive"))
      (node (ref "S257") (pin "1") (pinfunction "1_1") (pintype "passive"))
    )
    (net (code "3") (name "/col2") (class "Default")
      (node (ref "S202") (pin "2") (pinfunction "2_2") (pintype "passive"))
      (node (ref "S216") (pin "2") (pinfunction "2_2") (pintype "passive"))
      (node (ref "S230") (pin "2") (pinfunction "2_2") (pintype "passive"))
      (node (ref "S244") (pin "1") (pinfunction "1_1") (pintype "passive"))
      (node (ref "S258") (pin "2") (pinfunction "2_2") (pintype "passive"))
    )
    (net (code "4") (name "/col3") (class "Default")
      (node (ref "S203") (pin "2") (pinfunction "2_2") (pintype "passive"))
      (node (ref "S217") (pin "2") (pinfunction "2_2") (pintype "passive"))
      (node (ref "S231") (pin "2") (pinfunction "2_2") (pintype "passive"))
      (node (ref "S245") (pin "2") (pinfunction "2_2") (pintype "passive"))
      (node (ref "S260") (pin "2") (pinfunction "2_2") (pintype "passive"))
      (node (ref "S260_1") (pin "2") (pinfunction "2_2") (pintype "passive"))
    )
    (net (code "5") (name "/col4") (class "Default")
      (node (ref "S204") (pin "2") (pinfunction "2_2") (pintype "passive"))
      (node (ref "S218") (pin "2") (pinfunction "2_2") (pintype "passive"))
      (node (ref "S232") (pin "2") (pinfunction "2_2") (pintype "passive"))
      (node (ref "S246") (pin "2") (pinfunction "2_2") (pintype "passive"))
    )
    (net (code "6") (name "/col5") (class "Default")
      (node (ref "S205") (pin "2") (pinfunction "2_2") (pintype "passive"))
      (node (ref "S219") (pin "2") (pinfunction "2_2") (pintype "passive"))
      (node (ref "S233") (pin "2") (pinfunction "2_2") (pintype "passive"))
      (node (ref "S247") (pin "2") (pinfunction "2_2") (pintype "passive"))
      (node (ref "S261") (pin "2") (pinfunction "2_2") (pintype "passive"))
      (node (ref "S261_1") (pin "2") (pinfunction "2_2") (pintype "passive"))
      (node (ref "S261_2") (pin "1") (pinfunction "1_1") (pintype "passive"))
    )
    (net (code "7") (name "/col6") (class "Default")
      (node (ref "S206") (pin "2") (pinfunction "2_2") (pintype "passive"))
      (node (ref "S220") (pin "2") (pinfunction "2_2") (pintype "passive"))
      (node (ref "S234") (pin "2") (pinfunction "2_2") (pintype "passive"))
      (node (ref "S248") (pin "2") (pinfunction "2_2") (pintype "passive"))
    )
    (net (code "8") (name "/col7") (class "Default")
      (node (ref "S207") (pin "2") (pinfunction "2_2") (pintype "passive"))
      (node (ref "S221") (pin "2") (pinfunction "2_2") (pintype "passive"))
      (node (ref "S235") (pin "2") (pinfunction "2_2") (pintype "passive"))
      (node (ref "S249") (pin "2") (pinfunction "2_2") (pintype "passive"))
      (node (ref "S262") (pin "1") (pinfunction "1_1") (pintype "passive"))
      (node (ref "S262_1") (pin "1") (pinfunction "1_1") (pintype "passive"))
    )
    (net (code "9") (name "/col8") (class "Default")
      (node (ref "S208") (pin "2") (pinfunction "2_2") (pintype "passive"))
      (node (ref "S222") (pin "2") (pinfunction "2_2") (pintype "passive"))
      (node (ref "S236") (pin "2") (pinfunction "2_2") (pintype "passive"))
      (node (ref "S250") (pin "2") (pinfunction "2_2") (pintype "passive"))
    )
    (net (code "10") (name "/col9") (class "Default")
      (node (ref "S209") (pin "2") (pinfunction "2_2") (pintype "passive"))
      (node (ref "S223") (pin "2") (pinfunction "2_2") (pintype "passive"))
      (node (ref "S237") (pin "2") (pinfunction "2_2") (pintype "passive"))
      (node (ref "S251") (pin "2") (pinfunction "2_2") (pintype "passive"))
      (node (ref "S263") (pin "1") (pinfunction "1_1") (pintype "passive"))
      (node (ref "S263_1") (pin "1") (pinfunction "1_1") (pintype "passive"))
    )
    (net (code "11") (name "/col10") (class "Default")
      (node (ref "S210") (pin "2") (pinfunction "2_2") (pintype "passive"))
      (node (ref "S224") (pin "2") (pinfunction "2_2") (pintype "passive"))
      (node (ref "S238") (pin "2") (pinfunction "2_2") (pintype "passive"))
      (node (ref "S252") (pin "2") (pinfunction "2_2") (pintype "passive"))
      (node (ref "S264") (pin "2") (pinfunction "2_2") (pintype "passive"))
    )
    (net (code "12") (name "/col11") (class "Default")
      (node (ref "S211") (pin "2") (pinfunction "2_2") (pintype "passive"))
      (node (ref "S225") (pin "2") (pinfunction "2_2") (pintype "passive"))
      (node (ref "S239") (pin "2") (pinfunction "2_2") (pintype "passive"))
      (node (ref "S253") (pin "2") (pinfunction "2_2") (pintype "passive"))
      (node (ref "S265") (pin "1") (pinfunction "1_1") (pintype "passive"))
    )
    (net (code "13") (name "/col12") (class "Default")
      (node (ref "S212") (pin "2") (pinfunction "2_2") (pintype "passive"))
      (node (ref "S226") (pin "2") (pinfunction "2_2") (pintype "passive"))
      (node (ref "S240") (pin "2") (pinfunction "2_2") (pintype "passive"))
      (node (ref "S241") (pin "1") (pinfunction "1_1") (pintype "passive"))
      (node (ref "S254") (pin "2") (pinfunction "2_2") (pintype "passive"))
    )
    (net (code "14") (name "/col13") (class "Default")
      (node (ref "S213") (pin "2") (pinfunction "2_2") (pintype "passive"))
      (node (ref "S227") (pin "2") (pinfunction "2_2") (pintype "passive"))
      (node (ref "S228_2") (pin "2") (pinfunction "2_2") (pintype "passive"))
      (node (ref "S256") (pin "2") (pinfunction "2_2") (pintype "passive"))
      (node (ref "S266") (pin "2") (pinfunction "2_2") (pintype "passive"))
    )
    (net (code "15") (name "/col14") (class "Default")
      (node (ref "S214") (pin "2") (pinfunction "2_2") (pintype "passive"))
      (node (ref "S228") (pin "2") (pinfunction "2_2") (pintype "passive"))
      (node (ref "S242") (pin "2") (pinfunction "2_2") (pintype "passive"))
      (node (ref "S259") (pin "2") (pinfunction "2_2") (pintype "passive"))
      (node (ref "S269") (pin "2") (pinfunction "2_2") (pintype "passive"))
    )
    (net (code "16") (name "/row1") (class "Default")
      (node (ref "D201") (pin "2") (pinfunction "K_2") (pintype "passive"))
      (node (ref "D202") (pin "2") (pinfunction "K_2") (pintype "passive"))
      (node (ref "D203") (pin "2") (pinfunction "K_2") (pintype "passive"))
      (node (ref "D204") (pin "2") (pinfunction "K_2") (pintype "passive"))
      (node (ref "D205") (pin "2") (pinfunction "K_2") (pintype "passive"))
      (node (ref "D206") (pin "2") (pinfunction "K_2") (pintype "passive"))
      (node (ref "D207") (pin "2") (pinfunction "K_2") (pintype "passive"))
      (node (ref "D208") (pin "2") (pinfunction "K_2") (pintype "passive"))
      (node (ref "D209") (pin "2") (pinfunction "K_2") (pintype "passive"))
      (node (ref "D210") (pin "2") (pinfunction "K_2") (pintype "passive"))
      (node (ref "D211") (pin "2") (pinfunction "K_2") (pintype "passive"))
      (node (ref "D212") (pin "2") (pinfunction "K_2") (pintype "passive"))
      (node (ref "D213") (pin "2") (pinfunction "K_2") (pintype "passive"))
      (node (ref "D214") (pin "2") (pinfunction "K_2") (pintype "passive"))
    )
    (net (code "17") (name "/row2") (class "Default")
      (node (ref "D215") (pin "2") (pinfunction "K_2") (pintype "passive"))
      (node (ref "D216") (pin "2") (pinfunction "K_2") (pintype "passive"))
      (node (ref "D217") (pin "2") (pinfunction "K_2") (pintype "passive"))
      (node (ref "D218") (pin "2") (pinfunction "K_2") (pintype "passive"))
      (node (ref "D219") (pin "2") (pinfunction "K_2") (pintype "passive"))
      (node (ref "D220") (pin "2") (pinfunction "K_2") (pintype "passive"))
      (node (ref "D221") (pin "2") (pinfunction "K_2") (pintype "passive"))
      (node (ref "D222") (pin "2") (pinfunction "K_2") (pintype "passive"))
      (node (ref "D223") (pin "2") (pinfunction "K_2") (pintype "passive"))
      (node (ref "D224") (pin "2") (pinfunction "K_2") (pintype "passive"))
      (node (ref "D225") (pin "2") (pinfunction "K_2") (pintype "passive"))
      (node (ref "D226") (pin "2") (pinfunction "K_2") (pintype "passive"))
      (node (ref "D227") (pin "2") (pinfunction "K_2") (pintype "passive"))
      (node (ref "D228") (pin "2") (pinfunction "K_2") (pintype "passive"))
    )
    (net (code "18") (name "/row3") (class "Default")
      (node (ref "D228_2") (pin "2") (pinfunction "K_2") (pintype "passive"))
      (node (ref "D229") (pin "2") (pinfunction "K_2") (pintype "passive"))
      (node (ref "D230") (pin "2") (pinfunction "K_2") (pintype "passive"))
      (node (ref "D231") (pin "2") (pinfunction "K_2") (pintype "passive"))
      (node (ref "D232") (pin "2") (pinfunction "K_2") (pintype "passive"))
      (node (ref "D233") (pin "2") (pinfunction "K_2") (pintype "passive"))
      (node (ref "D234") (pin "2") (pinfunction "K_2") (pintype "passive"))
      (node (ref "D235") (pin "2") (pinfunction "K_2") (pintype "passive"))
      (node (ref "D236") (pin "2") (pinfunction "K_2") (pintype "passive"))
      (node (ref "D237") (pin "2") (pinfunction "K_2") (pintype "passive"))
      (node (ref "D238") (pin "2") (pinfunction "K_2") (pintype "passive"))
      (node (ref "D239") (pin "2") (pinfunction "K_2") (pintype "passive"))
      (node (ref "D240") (pin "2") (pinfunction "K_2") (pintype "passive"))
      (node (ref "D259") (pin "2") (pinfunction "K_2") (pintype "passive"))
    )
    (net (code "19") (name "/row4") (class "Default")
      (node (ref "D242") (pin "2") (pinfunction "K_2") (pintype "passive"))
      (node (ref "D243") (pin "2") (pinfunction "K_2") (pintype "passive"))
      (node (ref "D244") (pin "2") (pinfunction "K_2") (pintype "passive"))
      (node (ref "D245") (pin "2") (pinfunction "K_2") (pintype "passive"))
      (node (ref "D246") (pin "2") (pinfunction "K_2") (pintype "passive"))
      (node (ref "D247") (pin "2") (pinfunction "K_2") (pintype "passive"))
      (node (ref "D248") (pin "2") (pinfunction "K_2") (pintype "passive"))
      (node (ref "D249") (pin "2") (pinfunction "K_2") (pintype "passive"))
      (node (ref "D250") (pin "2") (pinfunction "K_2") (pintype "passive"))
      (node (ref "D251") (pin "2") (pinfunction "K_2") (pintype "passive"))
      (node (ref "D252") (pin "2") (pinfunction "K_2") (pintype "passive"))
      (node (ref "D253") (pin "2") (pinfunction "K_2") (pintype "passive"))
      (node (ref "D254") (pin "2") (pinfunction "K_2") (pintype "passive"))
      (node (ref "D255") (pin "2") (pinfunction "K_2") (pintype "passive"))
    )
    (net (code "20") (name "/row5") (class "Default")
      (node (ref "D241") (pin "2") (pinfunction "K_2") (pintype "passive"))
      (node (ref "D256") (pin "2") (pinfunction "K_2") (pintype "passive"))
      (node (ref "D257") (pin "2") (pinfunction "K_2") (pintype "passive"))
      (node (ref "D258") (pin "2") (pinfunction "K_2") (pintype "passive"))
      (node (ref "D260") (pin "2") (pinfunction "K_2") (pintype "passive"))
      (node (ref "D261") (pin "2") (pinfunction "K_2") (pintype "passive"))
      (node (ref "D262") (pin "2") (pinfunction "K_2") (pintype "passive"))
      (node (ref "D263") (pin "2") (pinfunction "K_2") (pintype "passive"))
      (node (ref "D264") (pin "2") (pinfunction "K_2") (pintype "passive"))
      (node (ref "D265") (pin "2") (pinfunction "K_2") (pintype "passive"))
      (node (ref "D266") (pin "2") (pinfunction "K_2") (pintype "passive"))
    )
    (net (code "21") (name "Net-(D201-A)") (class "Default")
      (node (ref "D201") (pin "1") (pinfunction "A_1") (pintype "passive"))
      (node (ref "S201") (pin "1") (pinfunction "1_1") (pintype "passive"))
    )
    (net (code "22") (name "Net-(D202-A)") (class "Default")
      (node (ref "D202") (pin "1") (pinfunction "A_1") (pintype "passive"))
      (node (ref "S202") (pin "1") (pinfunction "1_1") (pintype "passive"))
    )
    (net (code "23") (name "Net-(D203-A)") (class "Default")
      (node (ref "D203") (pin "1") (pinfunction "A_1") (pintype "passive"))
      (node (ref "S203") (pin "1") (pinfunction "1_1") (pintype "passive"))
    )
    (net (code "24") (name "Net-(D204-A)") (class "Default")
      (node (ref "D204") (pin "1") (pinfunction "A_1") (pintype "passive"))
      (node (ref "S204") (pin "1") (pinfunction "1_1") (pintype "passive"))
    )
    (net (code "25") (name "Net-(D205-A)") (class "Default")
      (node (ref "D205") (pin "1") (pinfunction "A_1") (pintype "passive"))
      (node (ref "S205") (pin "1") (pinfunction "1_1") (pintype "passive"))
    )
    (net (code "26") (name "Net-(D206-A)") (class "Default")
      (node (ref "D206") (pin "1") (pinfunction "A_1") (pintype "passive"))
      (node (ref "S206") (pin "1") (pinfunction "1_1") (pintype "passive"))
    )
    (net (code "27") (name "Net-(D207-A)") (class "Default")
      (node (ref "D207") (pin "1") (pinfunction "A_1") (pintype "passive"))
      (node (ref "S207") (pin "1") (pinfunction "1_1") (pintype "passive"))
    )
    (net (code "28") (name "Net-(D208-A)") (class "Default")
      (node (ref "D208") (pin "1") (pinfunction "A_1") (pintype "passive"))
      (node (ref "S208") (pin "1") (pinfunction "1_1") (pintype "passive"))
    )
    (net (code "29") (name "Net-(D209-A)") (class "Default")
      (node (ref "D209") (pin "1") (pinfunction "A_1") (pintype "passive"))
      (node (ref "S209") (pin "1") (pinfunction "1_1") (pintype "passive"))
    )
    (net (code "30") (name "Net-(D210-A)") (class "Default")
      (node (ref "D210") (pin "1") (pinfunction "A_1") (pintype "passive"))
      (node (ref "S210") (pin "1") (pinfunction "1_1") (pintype "passive"))
    )
    (net (code "31") (name "Net-(D211-A)") (class "Default")
      (node (ref "D211") (pin "1") (pinfunction "A_1") (pintype "passive"))
      (node (ref "S211") (pin "1") (pinfunction "1_1") (pintype "passive"))
    )
    (net (code "32") (name "Net-(D212-A)") (class "Default")
      (node (ref "D212") (pin "1") (pinfunction "A_1") (pintype "passive"))
      (node (ref "S212") (pin "1") (pinfunction "1_1") (pintype "passive"))
    )
    (net (code "33") (name "Net-(D213-A)") (class "Default")
      (node (ref "D213") (pin "1") (pinfunction "A_1") (pintype "passive"))
      (node (ref "S213") (pin "1") (pinfunction "1_1") (pintype "passive"))
    )
    (net (code "34") (name "Net-(D214-A)") (class "Default")
      (node (ref "D214") (pin "1") (pinfunction "A_1") (pintype "passive"))
      (node (ref "S214") (pin "1") (pinfunction "1_1") (pintype "passive"))
    )
    (net (code "35") (name "Net-(D215-A)") (class "Default")
      (node (ref "D215") (pin "1") (pinfunction "A_1") (pintype "passive"))
      (node (ref "S215") (pin "1") (pinfunction "1_1") (pintype "passive"))
    )
    (net (code "36") (name "Net-(D216-A)") (class "Default")
      (node (ref "D216") (pin "1") (pinfunction "A_1") (pintype "passive"))
      (node (ref "S216") (pin "1") (pinfunction "1_1") (pintype "passive"))
    )
    (net (code "37") (name "Net-(D217-A)") (class "Default")
      (node (ref "D217") (pin "1") (pinfunction "A_1") (pintype "passive"))
      (node (ref "S217") (pin "1") (pinfunction "1_1") (pintype "passive"))
    )
    (net (code "38") (name "Net-(D218-A)") (class "Default")
      (node (ref "D218") (pin "1") (pinfunction "A_1") (pintype "passive"))
      (node (ref "S218") (pin "1") (pinfunction "1_1") (pintype "passive"))
    )
    (net (code "39") (name "Net-(D219-A)") (class "Default")
      (node (ref "D219") (pin "1") (pinfunction "A_1") (pintype "passive"))
      (node (ref "S219") (pin "1") (pinfunction "1_1") (pintype "passive"))
    )
    (net (code "40") (name "Net-(D220-A)") (class "Default")
      (node (ref "D220") (pin "1") (pinfunction "A_1") (pintype "passive"))
      (node (ref "S220") (pin "1") (pinfunction "1_1") (pintype "passive"))
    )
    (net (code "41") (name "Net-(D221-A)") (class "Default")
      (node (ref "D221") (pin "1") (pinfunction "A_1") (pintype "passive"))
      (node (ref "S221") (pin "1") (pinfunction "1_1") (pintype "passive"))
    )
    (net (code "42") (name "Net-(D222-A)") (class "Default")
      (node (ref "D222") (pin "1") (pinfunction "A_1") (pintype "passive"))
      (node (ref "S222") (pin "1") (pinfunction "1_1") (pintype "passive"))
    )
    (net (code "43") (name "Net-(D223-A)") (class "Default")
      (node (ref "D223") (pin "1") (pinfunction "A_1") (pintype "passive"))
      (node (ref "S223") (pin "1") (pinfunction "1_1") (pintype "passive"))
    )
    (net (code "44") (name "Net-(D224-A)") (class "Default")
      (node (ref "D224") (pin "1") (pinfunction "A_1") (pintype "passive"))
      (node (ref "S224") (pin "1") (pinfunction "1_1") (pintype "passive"))
    )
    (net (code "45") (name "Net-(D225-A)") (class "Default")
      (node (ref "D225") (pin "1") (pinfunction "A_1") (pintype "passive"))
      (node (ref "S225") (pin "1") (pinfunction "1_1") (pintype "passive"))
    )
    (net (code "46") (name "Net-(D226-A)") (class "Default")
      (node (ref "D226") (pin "1") (pinfunction "A_1") (pintype "passive"))
      (node (ref "S226") (pin "1") (pinfunction "1_1") (pintype "passive"))
    )
    (net (code "47") (name "Net-(D227-A)") (class "Default")
      (node (ref "D227") (pin "1") (pinfunction "A_1") (pintype "passive"))
      (node (ref "S227") (pin "1") (pinfunction "1_1") (pintype "passive"))
    )
    (net (code "48") (name "Net-(D228-A)") (class "Default")
      (node (ref "D228") (pin "1") (pinfunction "A_1") (pintype "passive"))
      (node (ref "S228") (pin "1") (pinfunction "1_1") (pintype "passive"))
    )
    (net (code "49") (name "Net-(D228_2-A)") (class "Default")
      (node (ref "D228_2") (pin "1") (pinfunction "A_1") (pintype "passive"))
      (node (ref "S228_2") (pin "1") (pinfunction "1_1") (pintype "passive"))
    )
    (net (code "50") (name "Net-(D229-A)") (class "Default")
      (node (ref "D229") (pin "1") (pinfunction "A_1") (pintype "passive"))
      (node (ref "S229") (pin "2") (pinfunction "2_2") (pintype "passive"))
    )
    (net (code "51") (name "Net-(D230-A)") (class "Default")
      (node (ref "D230") (pin "1") (pinfunction "A_1") (pintype "passive"))
      (node (ref "S230") (pin "1") (pinfunction "1_1") (pintype "passive"))
    )
    (net (code "52") (name "Net-(D231-A)") (class "Default")
      (node (ref "D231") (pin "1") (pinfunction "A_1") (pintype "passive"))
      (node (ref "S231") (pin "1") (pinfunction "1_1") (pintype "passive"))
    )
    (net (code "53") (name "Net-(D232-A)") (class "Default")
      (node (ref "D232") (pin "1") (pinfunction "A_1") (pintype "passive"))
      (node (ref "S232") (pin "1") (pinfunction "1_1") (pintype "passive"))
    )
    (net (code "54") (name "Net-(D233-A)") (class "Default")
      (node (ref "D233") (pin "1") (pinfunction "A_1") (pintype "passive"))
      (node (ref "S233") (pin "1") (pinfunction "1_1") (pintype "passive"))
    )
    (net (code "55") (name "Net-(D234-A)") (class "Default")
      (node (ref "D234") (pin "1") (pinfunction "A_1") (pintype "passive"))
      (node (ref "S234") (pin "1") (pinfunction "1_1") (pintype "passive"))
    )
    (net (code "56") (name "Net-(D235-A)") (class "Default")
      (node (ref "D235") (pin "1") (pinfunction "A_1") (pintype "passive"))
      (node (ref "S235") (pin "1") (pinfunction "1_1") (pintype "passive"))
    )
    (net (code "57") (name "Net-(D236-A)") (class "Default")
      (node (ref "D236") (pin "1") (pinfunction "A_1") (pintype "passive"))
      (node (ref "S236") (pin "1") (pinfunction "1_1") (pintype "passive"))
    )
    (net (code "58") (name "Net-(D237-A)") (class "Default")
      (node (ref "D237") (pin "1") (pinfunction "A_1") (pintype "passive"))
      (node (ref "S237") (pin "1") (pinfunction "1_1") (pintype "passive"))
    )
    (net (code "59") (name "Net-(D238-A)") (class "Default")
      (node (ref "D238") (pin "1") (pinfunction "A_1") (pintype "passive"))
      (node (ref "S238") (pin "1") (pinfunction "1_1") (pintype "passive"))
    )
    (net (code "60") (name "Net-(D239-A)") (class "Default")
      (node (ref "D239") (pin "1") (pinfunction "A_1") (pintype "passive"))
      (node (ref "S239") (pin "1") (pinfunction "1_1") (pintype "passive"))
    )
    (net (code "61") (name "Net-(D240-A)") (class "Default")
      (node (ref "D240") (pin "1") (pinfunction "A_1") (pintype "passive"))
      (node (ref "S240") (pin "1") (pinfunction "1_1") (pintype "passive"))
    )
    (net (code "62") (name "Net-(D241-A)") (class "Default")
      (node (ref "D241") (pin "1") (pinfunction "A_1") (pintype "passive"))
      (node (ref "S241") (pin "2") (pinfunction "2_2") (pintype "passive"))
    )
    (net (code "63") (name "Net-(D242-A)") (class "Default")
      (node (ref "D242") (pin "1") (pinfunction "A_1") (pintype "passive"))
      (node (ref "S242") (pin "1") (pinfunction "1_1") (pintype "passive"))
    )
    (net (code "64") (name "Net-(D243-A)") (class "Default")
      (node (ref "D243") (pin "1") (pinfunction "A_1") (pintype "passive"))
      (node (ref "S243") (pin "1") (pinfunction "1_1") (pintype "passive"))
    )
    (net (code "65") (name "Net-(D244-A)") (class "Default")
      (node (ref "D244") (pin "1") (pinfunction "A_1") (pintype "passive"))
      (node (ref "S244") (pin "2") (pinfunction "2_2") (pintype "passive"))
    )
    (net (code "66") (name "Net-(D245-A)") (class "Default")
      (node (ref "D245") (pin "1") (pinfunction "A_1") (pintype "passive"))
      (node (ref "S245") (pin "1") (pinfunction "1_1") (pintype "passive"))
    )
    (net (code "67") (name "Net-(D246-A)") (class "Default")
      (node (ref "D246") (pin "1") (pinfunction "A_1") (pintype "passive"))
      (node (ref "S246") (pin "1") (pinfunction "1_1") (pintype "passive"))
    )
    (net (code "68") (name "Net-(D247-A)") (class "Default")
      (node (ref "D247") (pin "1") (pinfunction "A_1") (pintype "passive"))
      (node (ref "S247") (pin "1") (pinfunction "1_1") (pintype "passive"))
    )
    (net (code "69") (name "Net-(D248-A)") (class "Default")
      (node (ref "D248") (pin "1") (pinfunction "A_1") (pintype "passive"))
      (node (ref "S248") (pin "1") (pinfunction "1_1") (pintype "passive"))
    )
    (net (code "70") (name "Net-(D249-A)") (class "Default")
      (node (ref "D249") (pin "1") (pinfunction "A_1") (pintype "passive"))
      (node (ref "S249") (pin "1") (pinfunction "1_1") (pintype "passive"))
    )
    (net (code "71") (name "Net-(D250-A)") (class "Default")
      (node (ref "D250") (pin "1") (pinfunction "A_1") (pintype "passive"))
      (node (ref "S250") (pin "1") (pinfunction "1_1") (pintype "passive"))
    )
    (net (code "72") (name "Net-(D251-A)") (class "Default")
      (node (ref "D251") (pin "1") (pinfunction "A_1") (pintype "passive"))
      (node (ref "S251") (pin "1") (pinfunction "1_1") (pintype "passive"))
    )
    (net (code "73") (name "Net-(D252-A)") (class "Default")
      (node (ref "D252") (pin "1") (pinfunction "A_1") (pintype "passive"))
      (node (ref "S252") (pin "1") (pinfunction "1_1") (pintype "passive"))
    )
    (net (code "74") (name "Net-(D253-A)") (class "Default")
      (node (ref "D253") (pin "1") (pinfunction "A_1") (pintype "passive"))
      (node (ref "S253") (pin "1") (pinfunction "1_1") (pintype "passive"))
    )
    (net (code "75") (name "Net-(D254-A)") (class "Default")
      (node (ref "D254") (pin "1") (pinfunction "A_1") (pintype "passive"))
      (node (ref "S254") (pin "1") (pinfunction "1_1") (pintype "passive"))
    )
    (net (code "76") (name "Net-(D255-A)") (class "Default")
      (node (ref "D255") (pin "1") (pinfunction "A_1") (pintype "passive"))
      (node (ref "S256") (pin "1") (pinfunction "1_1") (pintype "passive"))
    )
    (net (code "77") (name "Net-(D256-A)") (class "Default")
      (node (ref "D256") (pin "1") (pinfunction "A_1") (pintype "passive"))
      (node (ref "S269") (pin "1") (pinfunction "1_1") (pintype "passive"))
    )
    (net (code "78") (name "Net-(D257-A)") (class "Default")
      (node (ref "D257") (pin "1") (pinfunction "A_1") (pintype "passive"))
      (node (ref "S257") (pin "2") (pinfunction "2_2") (pintype "passive"))
    )
    (net (code "79") (name "Net-(D258-A)") (class "Default")
      (node (ref "D258") (pin "1") (pinfunction "A_1") (pintype "passive"))
      (node (ref "S258") (pin "1") (pinfunction "1_1") (pintype "passive"))
    )
    (net (code "80") (name "Net-(D260-A)") (class "Default")
      (node (ref "D260") (pin "1") (pinfunction "A_1") (pintype "passive"))
      (node (ref "S260") (pin "1") (pinfunction "1_1") (pintype "passive"))
      (node (ref "S260_1") (pin "1") (pinfunction "1_1") (pintype "passive"))
    )
    (net (code "81") (name "Net-(D261-A)") (class "Default")
      (node (ref "D261") (pin "1") (pinfunction "A_1") (pintype "passive"))
      (node (ref "S261") (pin "1") (pinfunction "1_1") (pintype "passive"))
      (node (ref "S261_1") (pin "1") (pinfunction "1_1") (pintype "passive"))
      (node (ref "S261_2") (pin "1") (pinfunction "1_1") (pintype "passive"))
    )
    (net (code "82") (name "Net-(D262-A)") (class "Default")
      (node (ref "D262") (pin "1") (pinfunction "A_1") (pintype "passive"))
      (node (ref "S262") (pin "2") (pinfunction "2_2") (pintype "passive"))
      (node (ref "S262_1") (pin "2") (pinfunction "2_2") (pintype "passive"))
    )
    (net (code "83") (name "Net-(D263-A)") (class "Default")
      (node (ref "D263") (pin "1") (pinfunction "A_1") (pintype "passive"))
      (node (ref "S263") (pin "2") (pinfunction "2_2") (pintype "passive"))
      (node (ref "S263_1") (pin "2") (pinfunction "2_2") (pintype "passive"))
    )
    (net (code "84") (name "Net-(D264-A)") (class "Default")
      (node (ref "D264") (pin "1") (pinfunction "A_1") (pintype "passive"))
      (node (ref "S264") (pin "1") (pinfunction "1_1") (pintype "passive"))
    )
    (net (code "85") (name "Net-(D265-A)") (class "Default")
      (node (ref "D265") (pin "1") (pinfunction "A_1") (pintype "passive"))
      (node (ref "S265") (pin "2") (pinfunction "2_2") (pintype "passive"))
    )
    (net (code "86") (name "Net-(D266-A)") (class "Default")
      (node (ref "D266") (pin "1") (pinfunction "A_1") (pintype "passive"))
      (node (ref "S266") (pin "1") (pinfunction "1_1") (pintype "passive"))
    )
    (net (code "87") (name "unconnected-(STAB1-Pad1)") (class "Default")
      (node (ref "STAB1") (pin "1") (pinfunction "1_1") (pintype "passive"))
    )
  )
)
